# SW7201.net
KiCad netlist of a schematic drawn in Altium Designer
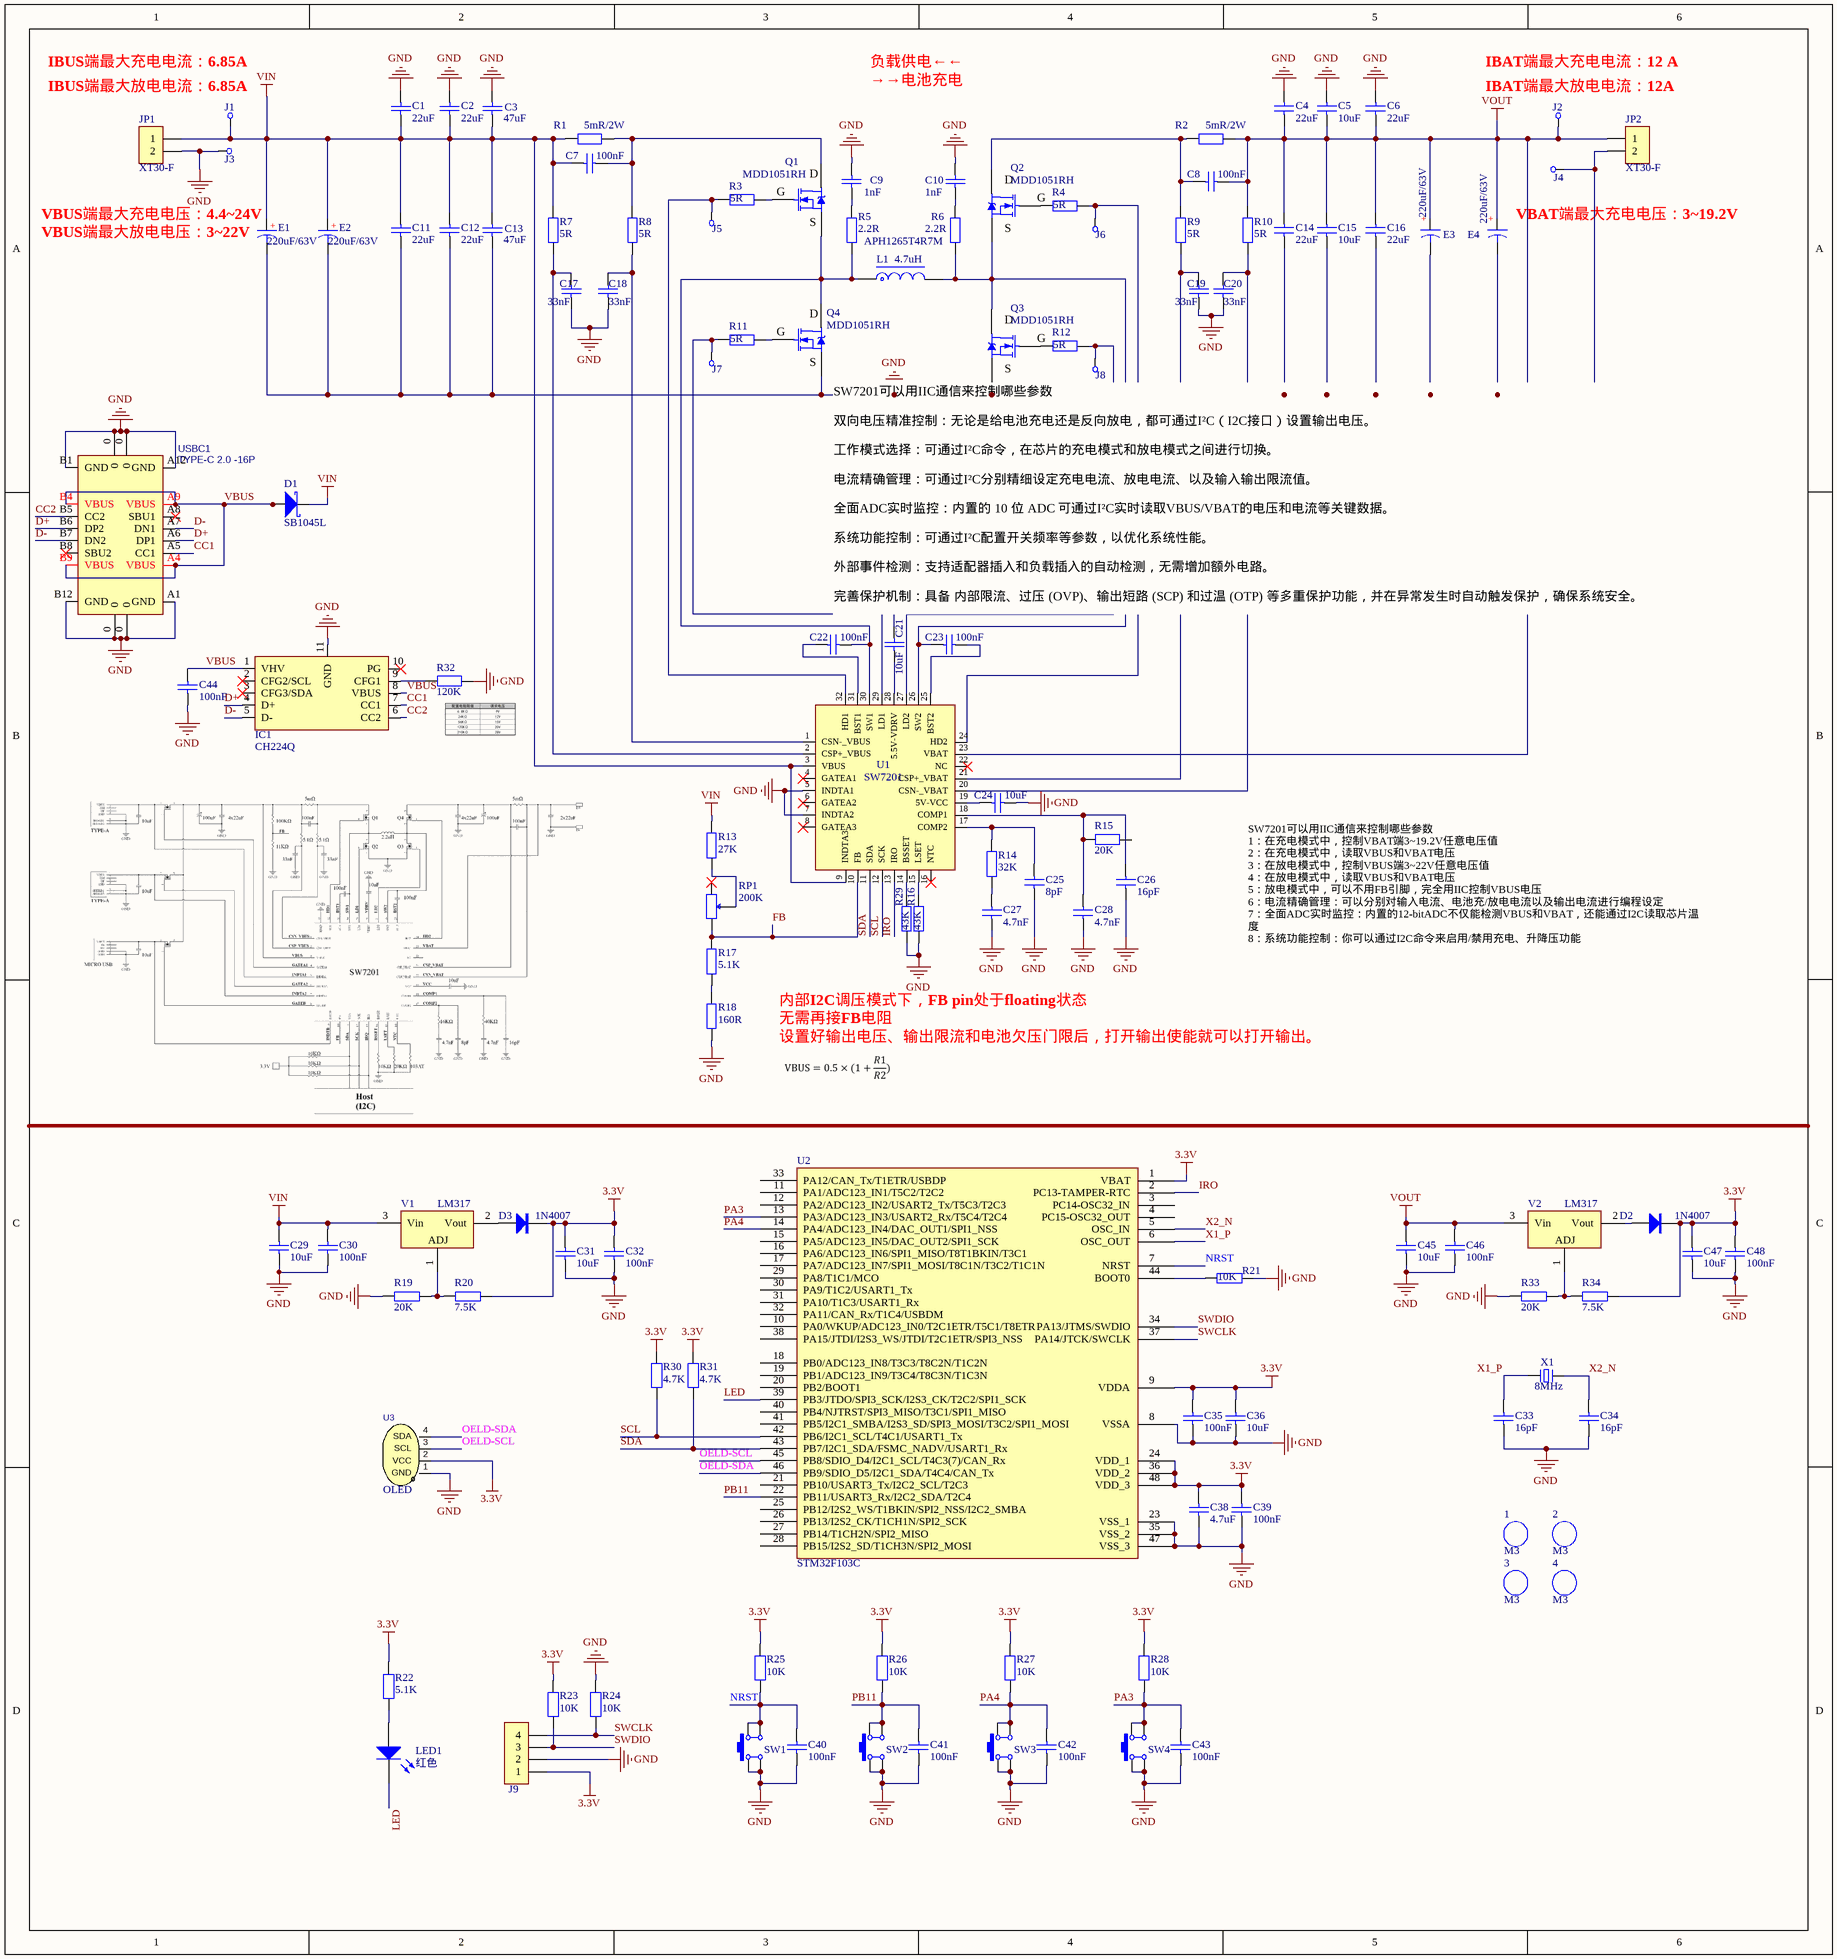
[diagram p0: SW7201.SchDoc]

(export (version "E")
  (design (tool "Eeschema 10.0.6"))
  (components
    (comp (ref "1")
      (value "M3")
      (footprint "M3 125X200")
      (description "铜柱孔")
      (libsource (lib "0.5 - 按键_开关_蜂鸣器_电池_测试点_Mark点_铜柱") (part "M3"))
    )
    (comp (ref "2")
      (value "M3")
      (footprint "M3 125X200")
      (description "铜柱孔")
      (libsource (lib "0.5 - 按键_开关_蜂鸣器_电池_测试点_Mark点_铜柱") (part "M3"))
    )
    (comp (ref "3")
      (value "M3")
      (footprint "M3 125X200")
      (description "铜柱孔")
      (libsource (lib "0.5 - 按键_开关_蜂鸣器_电池_测试点_Mark点_铜柱") (part "M3"))
    )
    (comp (ref "4")
      (value "M3")
      (footprint "M3 125X200")
      (description "铜柱孔")
      (libsource (lib "0.5 - 按键_开关_蜂鸣器_电池_测试点_Mark点_铜柱") (part "M3"))
    )
    (comp (ref "C1")
      (value "22uF")
      (footprint "C0805_L")
      (description "贴片电容/MLCC电容")
      (libsource (lib "0.1 - 电阻-电容-电感-保险丝-晶振-晶体-磁珠-电位器-法拉电容-馈通电容") (part "C"))
    )
    (comp (ref "C2")
      (value "22uF")
      (footprint "C0805_L")
      (description "贴片电容/MLCC电容")
      (libsource (lib "0.1 - 电阻-电容-电感-保险丝-晶振-晶体-磁珠-电位器-法拉电容-馈通电容") (part "C"))
    )
    (comp (ref "C3")
      (value "47uF")
      (footprint "C0805_L")
      (description "贴片电容/MLCC电容")
      (libsource (lib "0.1 - 电阻-电容-电感-保险丝-晶振-晶体-磁珠-电位器-法拉电容-馈通电容") (part "C"))
    )
    (comp (ref "C4")
      (value "22uF")
      (footprint "C0805_L")
      (description "贴片电容/MLCC电容")
      (libsource (lib "0.1 - 电阻-电容-电感-保险丝-晶振-晶体-磁珠-电位器-法拉电容-馈通电容") (part "C"))
    )
    (comp (ref "C5")
      (value "10uF")
      (footprint "C0805_L")
      (description "贴片电容/MLCC电容")
      (libsource (lib "0.1 - 电阻-电容-电感-保险丝-晶振-晶体-磁珠-电位器-法拉电容-馈通电容") (part "C"))
    )
    (comp (ref "C6")
      (value "22uF")
      (footprint "C0805_L")
      (description "贴片电容/MLCC电容")
      (libsource (lib "0.1 - 电阻-电容-电感-保险丝-晶振-晶体-磁珠-电位器-法拉电容-馈通电容") (part "C"))
    )
    (comp (ref "C7")
      (value "100nF")
      (footprint "C0805_L")
      (description "贴片电容/MLCC电容")
      (libsource (lib "0.1 - 电阻-电容-电感-保险丝-晶振-晶体-磁珠-电位器-法拉电容-馈通电容") (part "C"))
    )
    (comp (ref "C8")
      (value "100nF")
      (footprint "C0805_L")
      (description "贴片电容/MLCC电容")
      (libsource (lib "0.1 - 电阻-电容-电感-保险丝-晶振-晶体-磁珠-电位器-法拉电容-馈通电容") (part "C"))
    )
    (comp (ref "C9")
      (value "1nF")
      (footprint "C0805_L")
      (description "贴片电容/MLCC电容")
      (libsource (lib "0.1 - 电阻-电容-电感-保险丝-晶振-晶体-磁珠-电位器-法拉电容-馈通电容") (part "C"))
    )
    (comp (ref "C10")
      (value "1nF")
      (footprint "C0805_L")
      (description "贴片电容/MLCC电容")
      (libsource (lib "0.1 - 电阻-电容-电感-保险丝-晶振-晶体-磁珠-电位器-法拉电容-馈通电容") (part "C"))
    )
    (comp (ref "C11")
      (value "22uF")
      (footprint "C0805_L")
      (description "贴片电容/MLCC电容")
      (libsource (lib "0.1 - 电阻-电容-电感-保险丝-晶振-晶体-磁珠-电位器-法拉电容-馈通电容") (part "C"))
    )
    (comp (ref "C12")
      (value "22uF")
      (footprint "C0805_L")
      (description "贴片电容/MLCC电容")
      (libsource (lib "0.1 - 电阻-电容-电感-保险丝-晶振-晶体-磁珠-电位器-法拉电容-馈通电容") (part "C"))
    )
    (comp (ref "C13")
      (value "47uF")
      (footprint "C0805_L")
      (description "贴片电容/MLCC电容")
      (libsource (lib "0.1 - 电阻-电容-电感-保险丝-晶振-晶体-磁珠-电位器-法拉电容-馈通电容") (part "C"))
    )
    (comp (ref "C14")
      (value "22uF")
      (footprint "C0805_L")
      (description "贴片电容/MLCC电容")
      (libsource (lib "0.1 - 电阻-电容-电感-保险丝-晶振-晶体-磁珠-电位器-法拉电容-馈通电容") (part "C"))
    )
    (comp (ref "C15")
      (value "10uF")
      (footprint "C0805_L")
      (description "贴片电容/MLCC电容")
      (libsource (lib "0.1 - 电阻-电容-电感-保险丝-晶振-晶体-磁珠-电位器-法拉电容-馈通电容") (part "C"))
    )
    (comp (ref "C16")
      (value "22uF")
      (footprint "C0805_L")
      (description "贴片电容/MLCC电容")
      (libsource (lib "0.1 - 电阻-电容-电感-保险丝-晶振-晶体-磁珠-电位器-法拉电容-馈通电容") (part "C"))
    )
    (comp (ref "C17")
      (value "33nF")
      (footprint "C0805_L")
      (description "贴片电容/MLCC电容")
      (libsource (lib "0.1 - 电阻-电容-电感-保险丝-晶振-晶体-磁珠-电位器-法拉电容-馈通电容") (part "C"))
    )
    (comp (ref "C18")
      (value "33nF")
      (footprint "C0805_L")
      (description "贴片电容/MLCC电容")
      (libsource (lib "0.1 - 电阻-电容-电感-保险丝-晶振-晶体-磁珠-电位器-法拉电容-馈通电容") (part "C"))
    )
    (comp (ref "C19")
      (value "33nF")
      (footprint "C0805_L")
      (description "贴片电容/MLCC电容")
      (libsource (lib "0.1 - 电阻-电容-电感-保险丝-晶振-晶体-磁珠-电位器-法拉电容-馈通电容") (part "C"))
    )
    (comp (ref "C20")
      (value "33nF")
      (footprint "C0805_L")
      (description "贴片电容/MLCC电容")
      (libsource (lib "0.1 - 电阻-电容-电感-保险丝-晶振-晶体-磁珠-电位器-法拉电容-馈通电容") (part "C"))
    )
    (comp (ref "C21")
      (value "10uF")
      (footprint "C0805_L")
      (description "贴片电容/MLCC电容")
      (libsource (lib "0.1 - 电阻-电容-电感-保险丝-晶振-晶体-磁珠-电位器-法拉电容-馈通电容") (part "C"))
    )
    (comp (ref "C22")
      (value "100nF")
      (footprint "C0805_L")
      (description "贴片电容/MLCC电容")
      (libsource (lib "0.1 - 电阻-电容-电感-保险丝-晶振-晶体-磁珠-电位器-法拉电容-馈通电容") (part "C"))
    )
    (comp (ref "C23")
      (value "100nF")
      (footprint "C0805_L")
      (description "贴片电容/MLCC电容")
      (libsource (lib "0.1 - 电阻-电容-电感-保险丝-晶振-晶体-磁珠-电位器-法拉电容-馈通电容") (part "C"))
    )
    (comp (ref "C24")
      (value "10uF")
      (footprint "C0805_L")
      (description "贴片电容/MLCC电容")
      (libsource (lib "0.1 - 电阻-电容-电感-保险丝-晶振-晶体-磁珠-电位器-法拉电容-馈通电容") (part "C"))
    )
    (comp (ref "C25")
      (value "8pF")
      (footprint "C0805_L")
      (description "贴片电容/MLCC电容")
      (libsource (lib "0.1 - 电阻-电容-电感-保险丝-晶振-晶体-磁珠-电位器-法拉电容-馈通电容") (part "C"))
    )
    (comp (ref "C26")
      (value "16pF")
      (footprint "C0805_L")
      (description "贴片电容/MLCC电容")
      (libsource (lib "0.1 - 电阻-电容-电感-保险丝-晶振-晶体-磁珠-电位器-法拉电容-馈通电容") (part "C"))
    )
    (comp (ref "C27")
      (value "4.7nF")
      (footprint "C0805_L")
      (description "贴片电容/MLCC电容")
      (libsource (lib "0.1 - 电阻-电容-电感-保险丝-晶振-晶体-磁珠-电位器-法拉电容-馈通电容") (part "C"))
    )
    (comp (ref "C28")
      (value "4.7nF")
      (footprint "C0805_L")
      (description "贴片电容/MLCC电容")
      (libsource (lib "0.1 - 电阻-电容-电感-保险丝-晶振-晶体-磁珠-电位器-法拉电容-馈通电容") (part "C"))
    )
    (comp (ref "C29")
      (value "10uF")
      (footprint "C0805_L")
      (description "贴片电容/MLCC电容")
      (libsource (lib "0.1 - 电阻-电容-电感-保险丝-晶振-晶体-磁珠-电位器-法拉电容-馈通电容") (part "C"))
    )
    (comp (ref "C30")
      (value "100nF")
      (footprint "C0805_L")
      (description "贴片电容/MLCC电容")
      (libsource (lib "0.1 - 电阻-电容-电感-保险丝-晶振-晶体-磁珠-电位器-法拉电容-馈通电容") (part "C"))
    )
    (comp (ref "C31")
      (value "10uF")
      (footprint "C0805_L")
      (description "贴片电容/MLCC电容")
      (libsource (lib "0.1 - 电阻-电容-电感-保险丝-晶振-晶体-磁珠-电位器-法拉电容-馈通电容") (part "C"))
    )
    (comp (ref "C32")
      (value "100nF")
      (footprint "C0805_L")
      (description "贴片电容/MLCC电容")
      (libsource (lib "0.1 - 电阻-电容-电感-保险丝-晶振-晶体-磁珠-电位器-法拉电容-馈通电容") (part "C"))
    )
    (comp (ref "C33")
      (value "16pF")
      (footprint "C0805_L")
      (description "贴片电容/MLCC电容")
      (libsource (lib "0.1 - 电阻-电容-电感-保险丝-晶振-晶体-磁珠-电位器-法拉电容-馈通电容") (part "C"))
    )
    (comp (ref "C34")
      (value "16pF")
      (footprint "C0805_L")
      (description "贴片电容/MLCC电容")
      (libsource (lib "0.1 - 电阻-电容-电感-保险丝-晶振-晶体-磁珠-电位器-法拉电容-馈通电容") (part "C"))
    )
    (comp (ref "C35")
      (value "100nF")
      (footprint "C0805_L")
      (description "贴片电容/MLCC电容")
      (libsource (lib "0.1 - 电阻-电容-电感-保险丝-晶振-晶体-磁珠-电位器-法拉电容-馈通电容") (part "C"))
    )
    (comp (ref "C36")
      (value "10uF")
      (footprint "C0805_L")
      (description "贴片电容/MLCC电容")
      (libsource (lib "0.1 - 电阻-电容-电感-保险丝-晶振-晶体-磁珠-电位器-法拉电容-馈通电容") (part "C"))
    )
    (comp (ref "C38")
      (value "4.7uF")
      (footprint "C0805_L")
      (description "贴片电容/MLCC电容")
      (libsource (lib "0.1 - 电阻-电容-电感-保险丝-晶振-晶体-磁珠-电位器-法拉电容-馈通电容") (part "C"))
    )
    (comp (ref "C39")
      (value "100nF")
      (footprint "C0805_L")
      (description "贴片电容/MLCC电容")
      (libsource (lib "0.1 - 电阻-电容-电感-保险丝-晶振-晶体-磁珠-电位器-法拉电容-馈通电容") (part "C"))
    )
    (comp (ref "C40")
      (value "100nF")
      (footprint "C0805_L")
      (description "贴片电容/MLCC电容")
      (libsource (lib "0.1 - 电阻-电容-电感-保险丝-晶振-晶体-磁珠-电位器-法拉电容-馈通电容") (part "C"))
    )
    (comp (ref "C41")
      (value "100nF")
      (footprint "C0805_L")
      (description "贴片电容/MLCC电容")
      (libsource (lib "0.1 - 电阻-电容-电感-保险丝-晶振-晶体-磁珠-电位器-法拉电容-馈通电容") (part "C"))
    )
    (comp (ref "C42")
      (value "100nF")
      (footprint "C0805_L")
      (description "贴片电容/MLCC电容")
      (libsource (lib "0.1 - 电阻-电容-电感-保险丝-晶振-晶体-磁珠-电位器-法拉电容-馈通电容") (part "C"))
    )
    (comp (ref "C43")
      (value "100nF")
      (footprint "C0805_L")
      (description "贴片电容/MLCC电容")
      (libsource (lib "0.1 - 电阻-电容-电感-保险丝-晶振-晶体-磁珠-电位器-法拉电容-馈通电容") (part "C"))
    )
    (comp (ref "C44")
      (value "100nF")
      (footprint "C0805_L")
      (description "贴片电容/MLCC电容")
      (libsource (lib "0.1 - 电阻-电容-电感-保险丝-晶振-晶体-磁珠-电位器-法拉电容-馈通电容") (part "C"))
    )
    (comp (ref "C45")
      (value "10uF")
      (footprint "C0805_L")
      (description "贴片电容/MLCC电容")
      (libsource (lib "0.1 - 电阻-电容-电感-保险丝-晶振-晶体-磁珠-电位器-法拉电容-馈通电容") (part "C"))
    )
    (comp (ref "C46")
      (value "100nF")
      (footprint "C0805_L")
      (description "贴片电容/MLCC电容")
      (libsource (lib "0.1 - 电阻-电容-电感-保险丝-晶振-晶体-磁珠-电位器-法拉电容-馈通电容") (part "C"))
    )
    (comp (ref "C47")
      (value "10uF")
      (footprint "C0805_L")
      (description "贴片电容/MLCC电容")
      (libsource (lib "0.1 - 电阻-电容-电感-保险丝-晶振-晶体-磁珠-电位器-法拉电容-馈通电容") (part "C"))
    )
    (comp (ref "C48")
      (value "100nF")
      (footprint "C0805_L")
      (description "贴片电容/MLCC电容")
      (libsource (lib "0.1 - 电阻-电容-电感-保险丝-晶振-晶体-磁珠-电位器-法拉电容-馈通电容") (part "C"))
    )
    (comp (ref "D1")
      (value "SB1045L")
      (footprint "TO-277_3P-L5.4-W4.0")
      (libsource (lib "0.2 - 二极管-TVS-ESD-整流桥-放电管") (part "SB1045L"))
    )
    (comp (ref "D2")
      (value "1N4007")
      (footprint "SOD-123")
      (description "整流二极管")
      (libsource (lib "0.2 - 二极管-TVS-ESD-整流桥-放电管") (part "1N4007"))
    )
    (comp (ref "D3")
      (value "1N4007")
      (footprint "SOD-123")
      (description "整流二极管")
      (libsource (lib "0.2 - 二极管-TVS-ESD-整流桥-放电管") (part "1N4007"))
    )
    (comp (ref "E1")
      (value "220uF/63V")
      (footprint "CT 5.0*10*13 - R")
      (description "直插固态电容")
      (libsource (lib "") (part "CS_1"))
    )
    (comp (ref "E2")
      (value "220uF/63V")
      (footprint "CT 5.0*10*13 - R")
      (description "直插固态电容")
      (libsource (lib "") (part "CS_1"))
    )
    (comp (ref "E3")
      (value "220uF/63V")
      (footprint "CT 5.0*10*13 - R")
      (description "直插固态电容")
      (libsource (lib "0.1 - 电阻-电容-电感-保险丝-晶振-晶体-磁珠-电位器-法拉电容-馈通电容") (part "CS"))
    )
    (comp (ref "E4")
      (value "220uF/63V")
      (footprint "CT 5.0*10*13 - R")
      (description "直插固态电容")
      (libsource (lib "0.1 - 电阻-电容-电感-保险丝-晶振-晶体-磁珠-电位器-法拉电容-馈通电容") (part "CS"))
    )
    (comp (ref "IC1")
      (value "CH224Q")
      (footprint "DFN-10_L2.0-W2")
      (libsource (lib "1.8 - CH340系列编程器芯片") (part "CH224Q"))
    )
    (comp (ref "J1")
      (value "CHECK")
      (footprint "CHECK-A")
      (description "测试点")
      (libsource (lib "课程库") (part "CHECK"))
    )
    (comp (ref "J2")
      (value "CHECK")
      (footprint "CHECK-A")
      (description "测试点")
      (libsource (lib "课程库") (part "CHECK"))
    )
    (comp (ref "J3")
      (value "CHECK")
      (footprint "CHECK-A")
      (description "测试点")
      (libsource (lib "课程库") (part "CHECK"))
    )
    (comp (ref "J4")
      (value "CHECK")
      (footprint "CHECK-A")
      (description "测试点")
      (libsource (lib "课程库") (part "CHECK"))
    )
    (comp (ref "J5")
      (value "CHECK")
      (footprint "CHECK-A")
      (description "测试点")
      (libsource (lib "课程库") (part "CHECK"))
    )
    (comp (ref "J6")
      (value "CHECK")
      (footprint "CHECK-A")
      (description "测试点")
      (libsource (lib "课程库") (part "CHECK"))
    )
    (comp (ref "J7")
      (value "CHECK")
      (footprint "CHECK-A")
      (description "测试点")
      (libsource (lib "课程库") (part "CHECK"))
    )
    (comp (ref "J8")
      (value "CHECK")
      (footprint "CHECK-A")
      (description "测试点")
      (libsource (lib "课程库") (part "CHECK"))
    )
    (comp (ref "J9")
      (value "HDR-1X4")
      (footprint "HDR2.54-LI-4P")
      (description "4P接插件")
      (libsource (lib "5.5 - 2.54mm连接器(KF2EDGK_XH2.54_2.54排针排母)") (part "Header 4"))
    )
    (comp (ref "JP1")
      (value "XT30-F")
      (footprint "XT30PW-F")
      (description "XT30母座")
      (libsource (lib "") (part "XT30-F_1"))
    )
    (comp (ref "JP2")
      (value "XT30-F")
      (footprint "XT30PW-F")
      (description "XT30母座")
      (libsource (lib "0.6 - 电源_音频_USB Type-C_HDMI_XT60_5557_D-SUB_RJ45_SD-TF_SIM插座") (part "XT30-F"))
    )
    (comp (ref "L1")
      (value "4.7uH")
      (footprint "SMD,13.5x12.6mm")
      (description "一体成型电感")
      (libsource (lib "0.1 - 电阻-电容-电感-保险丝-晶振-晶体-磁珠-电位器-法拉电容-馈通电容") (part "L-Molding Choke"))
    )
    (comp (ref "LED1")
      (value "红色")
      (footprint "LED0805_G")
      (description "贴片LED")
      (libsource (lib "0.3 - LED发光二极管-IR二极管_接收管-光耦") (part "LED"))
    )
    (comp (ref "Q1")
      (value "MDD1051RH")
      (footprint "TO252")
      (description "N沟道 30V/80A")
      (libsource (lib "0.4 - 三极管-场效应管-可控硅") (part "NCE3080"))
    )
    (comp (ref "Q2")
      (value "MDD1051RH")
      (footprint "TO252")
      (description "N沟道 30V/80A")
      (libsource (lib "0.4 - 三极管-场效应管-可控硅") (part "NCE3080"))
    )
    (comp (ref "Q3")
      (value "MDD1051RH")
      (footprint "TO252")
      (description "N沟道 30V/80A")
      (libsource (lib "0.4 - 三极管-场效应管-可控硅") (part "NCE3080"))
    )
    (comp (ref "Q4")
      (value "MDD1051RH")
      (footprint "TO252")
      (description "N沟道 30V/80A")
      (libsource (lib "0.4 - 三极管-场效应管-可控硅") (part "NCE3080"))
    )
    (comp (ref "R1")
      (value "5mR/2W")
      (footprint "R2512_M")
      (description "贴片电阻")
      (libsource (lib "0.1 - 电阻-电容-电感-保险丝-晶振-晶体-磁珠-电位器-法拉电容-馈通电容") (part "R"))
    )
    (comp (ref "R2")
      (value "5mR/2W")
      (footprint "R2512_M")
      (description "贴片电阻")
      (libsource (lib "0.1 - 电阻-电容-电感-保险丝-晶振-晶体-磁珠-电位器-法拉电容-馈通电容") (part "R"))
    )
    (comp (ref "R3")
      (value "5R")
      (footprint "R0805_L")
      (description "贴片电阻")
      (libsource (lib "0.1 - 电阻-电容-电感-保险丝-晶振-晶体-磁珠-电位器-法拉电容-馈通电容") (part "R"))
    )
    (comp (ref "R4")
      (value "5R")
      (footprint "R0805_L")
      (description "贴片电阻")
      (libsource (lib "0.1 - 电阻-电容-电感-保险丝-晶振-晶体-磁珠-电位器-法拉电容-馈通电容") (part "R"))
    )
    (comp (ref "R5")
      (value "2.2R")
      (footprint "R0805_L")
      (description "贴片电阻")
      (libsource (lib "0.1 - 电阻-电容-电感-保险丝-晶振-晶体-磁珠-电位器-法拉电容-馈通电容") (part "R"))
    )
    (comp (ref "R6")
      (value "2.2R")
      (footprint "R0805_L")
      (description "贴片电阻")
      (libsource (lib "0.1 - 电阻-电容-电感-保险丝-晶振-晶体-磁珠-电位器-法拉电容-馈通电容") (part "R"))
    )
    (comp (ref "R7")
      (value "5R")
      (footprint "R0805_L")
      (description "贴片电阻")
      (libsource (lib "0.1 - 电阻-电容-电感-保险丝-晶振-晶体-磁珠-电位器-法拉电容-馈通电容") (part "R"))
    )
    (comp (ref "R8")
      (value "5R")
      (footprint "R0805_L")
      (description "贴片电阻")
      (libsource (lib "0.1 - 电阻-电容-电感-保险丝-晶振-晶体-磁珠-电位器-法拉电容-馈通电容") (part "R"))
    )
    (comp (ref "R9")
      (value "5R")
      (footprint "R0805_L")
      (description "贴片电阻")
      (libsource (lib "0.1 - 电阻-电容-电感-保险丝-晶振-晶体-磁珠-电位器-法拉电容-馈通电容") (part "R"))
    )
    (comp (ref "R10")
      (value "5R")
      (footprint "R0805_L")
      (description "贴片电阻")
      (libsource (lib "0.1 - 电阻-电容-电感-保险丝-晶振-晶体-磁珠-电位器-法拉电容-馈通电容") (part "R"))
    )
    (comp (ref "R11")
      (value "5R")
      (footprint "R0805_L")
      (description "贴片电阻")
      (libsource (lib "0.1 - 电阻-电容-电感-保险丝-晶振-晶体-磁珠-电位器-法拉电容-馈通电容") (part "R"))
    )
    (comp (ref "R12")
      (value "5R")
      (footprint "R0805_L")
      (description "贴片电阻")
      (libsource (lib "0.1 - 电阻-电容-电感-保险丝-晶振-晶体-磁珠-电位器-法拉电容-馈通电容") (part "R"))
    )
    (comp (ref "R13")
      (value "27K")
      (footprint "R0805_L")
      (description "贴片电阻")
      (libsource (lib "0.1 - 电阻-电容-电感-保险丝-晶振-晶体-磁珠-电位器-法拉电容-馈通电容") (part "R"))
    )
    (comp (ref "R14")
      (value "32K")
      (footprint "R0805_L")
      (description "贴片电阻")
      (libsource (lib "0.1 - 电阻-电容-电感-保险丝-晶振-晶体-磁珠-电位器-法拉电容-馈通电容") (part "R"))
    )
    (comp (ref "R15")
      (value "20K")
      (footprint "R0805_L")
      (description "贴片电阻")
      (libsource (lib "0.1 - 电阻-电容-电感-保险丝-晶振-晶体-磁珠-电位器-法拉电容-馈通电容") (part "R"))
    )
    (comp (ref "R16")
      (value "43K")
      (footprint "R0805_L")
      (description "贴片电阻")
      (libsource (lib "0.1 - 电阻-电容-电感-保险丝-晶振-晶体-磁珠-电位器-法拉电容-馈通电容") (part "R"))
    )
    (comp (ref "R17")
      (value "5.1K")
      (footprint "R0805_L")
      (description "贴片电阻")
      (libsource (lib "0.1 - 电阻-电容-电感-保险丝-晶振-晶体-磁珠-电位器-法拉电容-馈通电容") (part "R"))
    )
    (comp (ref "R18")
      (value "160R")
      (footprint "R0805_L")
      (description "贴片电阻")
      (libsource (lib "0.1 - 电阻-电容-电感-保险丝-晶振-晶体-磁珠-电位器-法拉电容-馈通电容") (part "R"))
    )
    (comp (ref "R19")
      (value "20K")
      (footprint "R0805_L")
      (description "贴片电阻")
      (libsource (lib "0.1 - 电阻-电容-电感-保险丝-晶振-晶体-磁珠-电位器-法拉电容-馈通电容") (part "R"))
    )
    (comp (ref "R20")
      (value "7.5K")
      (footprint "R0805_L")
      (description "贴片电阻")
      (libsource (lib "0.1 - 电阻-电容-电感-保险丝-晶振-晶体-磁珠-电位器-法拉电容-馈通电容") (part "R"))
    )
    (comp (ref "R21")
      (value "10K")
      (footprint "R0805_L")
      (description "贴片电阻")
      (libsource (lib "0.1 - 电阻-电容-电感-保险丝-晶振-晶体-磁珠-电位器-法拉电容-馈通电容") (part "R"))
    )
    (comp (ref "R22")
      (value "5.1K")
      (footprint "R0805_L")
      (description "贴片电阻")
      (libsource (lib "0.1 - 电阻-电容-电感-保险丝-晶振-晶体-磁珠-电位器-法拉电容-馈通电容") (part "R"))
    )
    (comp (ref "R23")
      (value "10K")
      (footprint "R0805_L")
      (description "贴片电阻")
      (libsource (lib "0.1 - 电阻-电容-电感-保险丝-晶振-晶体-磁珠-电位器-法拉电容-馈通电容") (part "R"))
    )
    (comp (ref "R24")
      (value "10K")
      (footprint "R0805_L")
      (description "贴片电阻")
      (libsource (lib "0.1 - 电阻-电容-电感-保险丝-晶振-晶体-磁珠-电位器-法拉电容-馈通电容") (part "R"))
    )
    (comp (ref "R25")
      (value "10K")
      (footprint "R0805_L")
      (description "贴片电阻")
      (libsource (lib "0.1 - 电阻-电容-电感-保险丝-晶振-晶体-磁珠-电位器-法拉电容-馈通电容") (part "R"))
    )
    (comp (ref "R26")
      (value "10K")
      (footprint "R0805_L")
      (description "贴片电阻")
      (libsource (lib "0.1 - 电阻-电容-电感-保险丝-晶振-晶体-磁珠-电位器-法拉电容-馈通电容") (part "R"))
    )
    (comp (ref "R27")
      (value "10K")
      (footprint "R0805_L")
      (description "贴片电阻")
      (libsource (lib "0.1 - 电阻-电容-电感-保险丝-晶振-晶体-磁珠-电位器-法拉电容-馈通电容") (part "R"))
    )
    (comp (ref "R28")
      (value "10K")
      (footprint "R0805_L")
      (description "贴片电阻")
      (libsource (lib "0.1 - 电阻-电容-电感-保险丝-晶振-晶体-磁珠-电位器-法拉电容-馈通电容") (part "R"))
    )
    (comp (ref "R29")
      (value "43K")
      (footprint "R0805_L")
      (description "贴片电阻")
      (libsource (lib "0.1 - 电阻-电容-电感-保险丝-晶振-晶体-磁珠-电位器-法拉电容-馈通电容") (part "R"))
    )
    (comp (ref "R30")
      (value "4.7K")
      (footprint "R0805_L")
      (description "贴片电阻")
      (libsource (lib "0.1 - 电阻-电容-电感-保险丝-晶振-晶体-磁珠-电位器-法拉电容-馈通电容") (part "R"))
    )
    (comp (ref "R31")
      (value "4.7K")
      (footprint "R0805_L")
      (description "贴片电阻")
      (libsource (lib "0.1 - 电阻-电容-电感-保险丝-晶振-晶体-磁珠-电位器-法拉电容-馈通电容") (part "R"))
    )
    (comp (ref "R32")
      (value "120K")
      (footprint "R0805_L")
      (description "贴片电阻")
      (libsource (lib "0.1 - 电阻-电容-电感-保险丝-晶振-晶体-磁珠-电位器-法拉电容-馈通电容") (part "R"))
    )
    (comp (ref "R33")
      (value "20K")
      (footprint "R0805_L")
      (description "贴片电阻")
      (libsource (lib "0.1 - 电阻-电容-电感-保险丝-晶振-晶体-磁珠-电位器-法拉电容-馈通电容") (part "R"))
    )
    (comp (ref "R34")
      (value "7.5K")
      (footprint "R0805_L")
      (description "贴片电阻")
      (libsource (lib "0.1 - 电阻-电容-电感-保险丝-晶振-晶体-磁珠-电位器-法拉电容-馈通电容") (part "R"))
    )
    (comp (ref "RP1")
      (value "200K")
      (footprint "3296W")
      (description "单联电位器")
      (libsource (lib "0.1 - 电阻-电容-电感-保险丝-晶振-晶体-磁珠-电位器-法拉电容-馈通电容") (part "RP"))
    )
    (comp (ref "SW1")
      (value "4.5x4.5x3.8")
      (footprint "SW SMD-4.5*4.5*3.8")
      (description "贴片4.5x4.5轻触开关")
      (libsource (lib "0.5 - 按键_开关_蜂鸣器_电池_测试点_Mark点_铜柱") (part "SW SMD-4.5x4.5"))
    )
    (comp (ref "SW2")
      (value "4.5x4.5x3.8")
      (footprint "SW SMD-4.5*4.5*3.8")
      (description "贴片4.5x4.5轻触开关")
      (libsource (lib "0.5 - 按键_开关_蜂鸣器_电池_测试点_Mark点_铜柱") (part "SW SMD-4.5x4.5"))
    )
    (comp (ref "SW3")
      (value "4.5x4.5x3.8")
      (footprint "SW SMD-4.5*4.5*3.8")
      (description "贴片4.5x4.5轻触开关")
      (libsource (lib "0.5 - 按键_开关_蜂鸣器_电池_测试点_Mark点_铜柱") (part "SW SMD-4.5x4.5"))
    )
    (comp (ref "SW4")
      (value "4.5x4.5x3.8")
      (footprint "SW SMD-4.5*4.5*3.8")
      (description "贴片4.5x4.5轻触开关")
      (libsource (lib "0.5 - 按键_开关_蜂鸣器_电池_测试点_Mark点_铜柱") (part "SW SMD-4.5x4.5"))
    )
    (comp (ref "U1")
      (value "SW7201")
      (footprint "QFN32_L4.0-W4.0-P0.4")
      (description "3~35V支持I2C控制的高效率双向升降压充放电控制器")
      (libsource (lib "0.7 - 电源类芯片") (part "SW7201"))
    )
    (comp (ref "U2")
      (value "STM32F103C")
      (footprint "LQFP-48_M")
      (description "STM32单片机48引脚")
      (libsource (lib "课程库") (part "STM32F103C"))
    )
    (comp (ref "U3")
      (value "OLED")
      (footprint "OLED")
      (description "0.96OLED")
      (libsource (lib "课程库") (part "OLED"))
    )
    (comp (ref "USBC1")
      (value "TYPE-C 2.0 -16P")
      (footprint "USB-C-SMD_16P")
      (description "USB2.0_Type-C_16Pin母座")
      (libsource (lib "0.6 - 电源_音频_USB Type-C_HDMI_XT60_5557_D-SUB_RJ45_SD-TF_SIM插座") (part "USB2.0_Type-C_16Pin"))
    )
    (comp (ref "V1")
      (value "LM317")
      (footprint "SOT223_M")
      (description "可调线性稳压芯片")
      (libsource (lib "0.7 - 电源类芯片") (part "LM317"))
    )
    (comp (ref "V2")
      (value "LM317")
      (footprint "SOT223_M")
      (description "可调线性稳压芯片")
      (libsource (lib "0.7 - 电源类芯片") (part "LM317"))
    )
    (comp (ref "X1")
      (value "8MHz")
      (footprint "XTAL-5032-2P")
      (description "2脚无源晶振(谐振器）")
      (libsource (lib "0.1 - 电阻-电容-电感-保险丝-晶振-晶体-磁珠-电位器-法拉电容-馈通电容") (part "XTAL-2P"))
    )
  )
  (nets
    (net (code "1") (name "/CC1") (class "Default")
      (node (ref "IC1") (pin "7") (pinfunction "CC1_7") (pintype "passive"))
      (node (ref "USBC1") (pin "A5") (pinfunction "CC1_A5") (pintype "passive"))
    )
    (net (code "2") (name "/CC2") (class "Default")
      (node (ref "IC1") (pin "6") (pinfunction "CC2_6") (pintype "passive"))
      (node (ref "USBC1") (pin "B5") (pinfunction "CC2_B5") (pintype "passive"))
    )
    (net (code "3") (name "/D+") (class "Default")
      (node (ref "IC1") (pin "4") (pinfunction "D+_4") (pintype "passive"))
      (node (ref "USBC1") (pin "A6") (pinfunction "DP1_A6") (pintype "passive"))
      (node (ref "USBC1") (pin "B6") (pinfunction "DP2_B6") (pintype "passive"))
    )
    (net (code "4") (name "/D-") (class "Default")
      (node (ref "IC1") (pin "5") (pinfunction "D-_5") (pintype "passive"))
      (node (ref "USBC1") (pin "A7") (pinfunction "DN1_A7") (pintype "passive"))
      (node (ref "USBC1") (pin "B7") (pinfunction "DN2_B7") (pintype "passive"))
    )
    (net (code "5") (name "/FB") (class "Default")
      (node (ref "R17") (pin "1") (pinfunction "1_1") (pintype "passive"))
      (node (ref "RP1") (pin "1") (pinfunction "1_1") (pintype "passive"))
      (node (ref "U1") (pin "10") (pinfunction "FB_10") (pintype "passive"))
    )
    (net (code "6") (name "/IRO") (class "Default")
      (node (ref "U1") (pin "13") (pinfunction "IRO_13") (pintype "passive"))
      (node (ref "U2") (pin "2") (pinfunction "PC13-TAMPER-RTC_2") (pintype "passive"))
    )
    (net (code "7") (name "/LED") (class "Default")
      (node (ref "LED1") (pin "2") (pinfunction "K_2") (pintype "passive"))
      (node (ref "U2") (pin "39") (pinfunction "PB3/JTDO/SPI3_SCK/I2S3_CK/T2C2/SPI1_SCK_39") (pintype "passive"))
    )
    (net (code "8") (name "/NRST") (class "Default")
      (node (ref "C40") (pin "2") (pinfunction "2_2") (pintype "passive"))
      (node (ref "R25") (pin "2") (pinfunction "2_2") (pintype "passive"))
      (node (ref "SW1") (pin "2") (pinfunction "2_2") (pintype "passive"))
      (node (ref "SW1") (pin "3") (pinfunction "3_3") (pintype "passive"))
      (node (ref "U2") (pin "7") (pinfunction "NRST_7") (pintype "passive"))
    )
    (net (code "9") (name "/OELD-SCL") (class "Default")
      (node (ref "U2") (pin "45") (pinfunction "PB8/SDIO_D4/I2C1_SCL/T4C3(7)/CAN_Rx_45") (pintype "passive"))
      (node (ref "U3") (pin "3") (pinfunction "SCL_3") (pintype "passive"))
    )
    (net (code "10") (name "/OELD-SDA") (class "Default")
      (node (ref "U2") (pin "46") (pinfunction "PB9/SDIO_D5/I2C1_SDA/T4C4/CAN_Tx_46") (pintype "passive"))
      (node (ref "U3") (pin "4") (pinfunction "SDA_4") (pintype "passive"))
    )
    (net (code "11") (name "/PA3") (class "Default")
      (node (ref "C43") (pin "2") (pinfunction "2_2") (pintype "passive"))
      (node (ref "R28") (pin "2") (pinfunction "2_2") (pintype "passive"))
      (node (ref "SW4") (pin "2") (pinfunction "2_2") (pintype "passive"))
      (node (ref "SW4") (pin "3") (pinfunction "3_3") (pintype "passive"))
      (node (ref "U2") (pin "13") (pinfunction "PA3/ADC123_IN3/USART2_Rx/T5C4/T2C4_13") (pintype "passive"))
    )
    (net (code "12") (name "/PA4") (class "Default")
      (node (ref "C42") (pin "2") (pinfunction "2_2") (pintype "passive"))
      (node (ref "R27") (pin "2") (pinfunction "2_2") (pintype "passive"))
      (node (ref "SW3") (pin "2") (pinfunction "2_2") (pintype "passive"))
      (node (ref "SW3") (pin "3") (pinfunction "3_3") (pintype "passive"))
      (node (ref "U2") (pin "14") (pinfunction "PA4/ADC123_IN4/DAC_OUT1/SPI1_NSS_14") (pintype "passive"))
    )
    (net (code "13") (name "/PB11") (class "Default")
      (node (ref "C41") (pin "2") (pinfunction "2_2") (pintype "passive"))
      (node (ref "R26") (pin "2") (pinfunction "2_2") (pintype "passive"))
      (node (ref "SW2") (pin "2") (pinfunction "2_2") (pintype "passive"))
      (node (ref "SW2") (pin "3") (pinfunction "3_3") (pintype "passive"))
      (node (ref "U2") (pin "22") (pinfunction "PB11/USART3_Rx/I2C2_SDA/T2C4_22") (pintype "passive"))
    )
    (net (code "14") (name "/SCL") (class "Default")
      (node (ref "R30") (pin "2") (pinfunction "2_2") (pintype "passive"))
      (node (ref "U1") (pin "12") (pinfunction "SCK_12") (pintype "passive"))
      (node (ref "U2") (pin "42") (pinfunction "PB6/I2C1_SCL/T4C1/USART1_Tx_42") (pintype "passive"))
    )
    (net (code "15") (name "/SDA") (class "Default")
      (node (ref "R31") (pin "2") (pinfunction "2_2") (pintype "passive"))
      (node (ref "U1") (pin "11") (pinfunction "SDA_11") (pintype "passive"))
      (node (ref "U2") (pin "43") (pinfunction "PB7/I2C1_SDA/FSMC_NADV/USART1_Rx_43") (pintype "passive"))
    )
    (net (code "16") (name "/SWCLK") (class "Default")
      (node (ref "J9") (pin "4") (pinfunction "4_4") (pintype "passive"))
      (node (ref "R24") (pin "2") (pinfunction "2_2") (pintype "passive"))
      (node (ref "U2") (pin "37") (pinfunction "PA14/JTCK/SWCLK_37") (pintype "passive"))
    )
    (net (code "17") (name "/SWDIO") (class "Default")
      (node (ref "J9") (pin "3") (pinfunction "3_3") (pintype "passive"))
      (node (ref "R23") (pin "2") (pinfunction "2_2") (pintype "passive"))
      (node (ref "U2") (pin "34") (pinfunction "PA13/JTMS/SWDIO_34") (pintype "passive"))
    )
    (net (code "18") (name "/VBUS") (class "Default")
      (node (ref "C44") (pin "2") (pinfunction "2_2") (pintype "passive"))
      (node (ref "D1") (pin "1") (pinfunction "A_1") (pintype "passive"))
      (node (ref "D1") (pin "3") (pinfunction "A_3") (pintype "passive"))
      (node (ref "IC1") (pin "1") (pinfunction "VHV_1") (pintype "passive"))
      (node (ref "IC1") (pin "8") (pinfunction "VBUS_8") (pintype "passive"))
      (node (ref "USBC1") (pin "A4") (pinfunction "VBUS_A4") (pintype "passive"))
      (node (ref "USBC1") (pin "A9") (pinfunction "VBUS_A9") (pintype "passive"))
      (node (ref "USBC1") (pin "B4") (pinfunction "VBUS_B4") (pintype "passive"))
      (node (ref "USBC1") (pin "B9") (pinfunction "VBUS_B9") (pintype "passive"))
    )
    (net (code "19") (name "/X1_P") (class "Default")
      (node (ref "C33") (pin "2") (pinfunction "2_2") (pintype "passive"))
      (node (ref "U2") (pin "6") (pinfunction "OSC_OUT_6") (pintype "passive"))
      (node (ref "X1") (pin "1") (pinfunction "1_1") (pintype "passive"))
    )
    (net (code "20") (name "/X2_N") (class "Default")
      (node (ref "C34") (pin "2") (pinfunction "2_2") (pintype "passive"))
      (node (ref "U2") (pin "5") (pinfunction "OSC_IN_5") (pintype "passive"))
      (node (ref "X1") (pin "2") (pinfunction "2_2") (pintype "passive"))
    )
    (net (code "21") (name "3.3V") (class "Default")
      (node (ref "C31") (pin "2") (pinfunction "2_2") (pintype "passive"))
      (node (ref "C32") (pin "2") (pinfunction "2_2") (pintype "passive"))
      (node (ref "C35") (pin "2") (pinfunction "2_2") (pintype "passive"))
      (node (ref "C36") (pin "2") (pinfunction "2_2") (pintype "passive"))
      (node (ref "C38") (pin "2") (pinfunction "2_2") (pintype "passive"))
      (node (ref "C39") (pin "2") (pinfunction "2_2") (pintype "passive"))
      (node (ref "C47") (pin "2") (pinfunction "2_2") (pintype "passive"))
      (node (ref "C48") (pin "2") (pinfunction "2_2") (pintype "passive"))
      (node (ref "D2") (pin "2") (pinfunction "K_2") (pintype "passive"))
      (node (ref "D3") (pin "2") (pinfunction "K_2") (pintype "passive"))
      (node (ref "J9") (pin "1") (pinfunction "1_1") (pintype "passive"))
      (node (ref "R20") (pin "2") (pinfunction "2_2") (pintype "passive"))
      (node (ref "R22") (pin "1") (pinfunction "1_1") (pintype "passive"))
      (node (ref "R23") (pin "1") (pinfunction "1_1") (pintype "passive"))
      (node (ref "R25") (pin "1") (pinfunction "1_1") (pintype "passive"))
      (node (ref "R26") (pin "1") (pinfunction "1_1") (pintype "passive"))
      (node (ref "R27") (pin "1") (pinfunction "1_1") (pintype "passive"))
      (node (ref "R28") (pin "1") (pinfunction "1_1") (pintype "passive"))
      (node (ref "R30") (pin "1") (pinfunction "1_1") (pintype "passive"))
      (node (ref "R31") (pin "1") (pinfunction "1_1") (pintype "passive"))
      (node (ref "R34") (pin "2") (pinfunction "2_2") (pintype "passive"))
      (node (ref "U2") (pin "1") (pinfunction "VBAT_1") (pintype "passive"))
      (node (ref "U2") (pin "24") (pinfunction "VDD_1_24") (pintype "passive"))
      (node (ref "U2") (pin "36") (pinfunction "VDD_2_36") (pintype "passive"))
      (node (ref "U2") (pin "48") (pinfunction "VDD_3_48") (pintype "passive"))
      (node (ref "U2") (pin "9") (pinfunction "VDDA_9") (pintype "passive"))
      (node (ref "U3") (pin "2") (pinfunction "VCC_2") (pintype "passive"))
    )
    (net (code "22") (name "GND") (class "Default")
      (node (ref "C1") (pin "2") (pinfunction "2_2") (pintype "passive"))
      (node (ref "C10") (pin "1") (pinfunction "1_1") (pintype "passive"))
      (node (ref "C11") (pin "1") (pinfunction "1_1") (pintype "passive"))
      (node (ref "C12") (pin "1") (pinfunction "1_1") (pintype "passive"))
      (node (ref "C13") (pin "1") (pinfunction "1_1") (pintype "passive"))
      (node (ref "C14") (pin "1") (pinfunction "1_1") (pintype "passive"))
      (node (ref "C15") (pin "1") (pinfunction "1_1") (pintype "passive"))
      (node (ref "C16") (pin "1") (pinfunction "1_1") (pintype "passive"))
      (node (ref "C17") (pin "2") (pinfunction "2_2") (pintype "passive"))
      (node (ref "C18") (pin "2") (pinfunction "2_2") (pintype "passive"))
      (node (ref "C19") (pin "2") (pinfunction "2_2") (pintype "passive"))
      (node (ref "C2") (pin "2") (pinfunction "2_2") (pintype "passive"))
      (node (ref "C20") (pin "2") (pinfunction "2_2") (pintype "passive"))
      (node (ref "C21") (pin "2") (pinfunction "2_2") (pintype "passive"))
      (node (ref "C24") (pin "1") (pinfunction "1_1") (pintype "passive"))
      (node (ref "C25") (pin "1") (pinfunction "1_1") (pintype "passive"))
      (node (ref "C26") (pin "1") (pinfunction "1_1") (pintype "passive"))
      (node (ref "C27") (pin "1") (pinfunction "1_1") (pintype "passive"))
      (node (ref "C28") (pin "1") (pinfunction "1_1") (pintype "passive"))
      (node (ref "C29") (pin "1") (pinfunction "1_1") (pintype "passive"))
      (node (ref "C3") (pin "2") (pinfunction "2_2") (pintype "passive"))
      (node (ref "C30") (pin "1") (pinfunction "1_1") (pintype "passive"))
      (node (ref "C31") (pin "1") (pinfunction "1_1") (pintype "passive"))
      (node (ref "C32") (pin "1") (pinfunction "1_1") (pintype "passive"))
      (node (ref "C33") (pin "1") (pinfunction "1_1") (pintype "passive"))
      (node (ref "C34") (pin "1") (pinfunction "1_1") (pintype "passive"))
      (node (ref "C35") (pin "1") (pinfunction "1_1") (pintype "passive"))
      (node (ref "C36") (pin "1") (pinfunction "1_1") (pintype "passive"))
      (node (ref "C38") (pin "1") (pinfunction "1_1") (pintype "passive"))
      (node (ref "C39") (pin "1") (pinfunction "1_1") (pintype "passive"))
      (node (ref "C4") (pin "2") (pinfunction "2_2") (pintype "passive"))
      (node (ref "C40") (pin "1") (pinfunction "1_1") (pintype "passive"))
      (node (ref "C41") (pin "1") (pinfunction "1_1") (pintype "passive"))
      (node (ref "C42") (pin "1") (pinfunction "1_1") (pintype "passive"))
      (node (ref "C43") (pin "1") (pinfunction "1_1") (pintype "passive"))
      (node (ref "C44") (pin "1") (pinfunction "1_1") (pintype "passive"))
      (node (ref "C45") (pin "1") (pinfunction "1_1") (pintype "passive"))
      (node (ref "C46") (pin "1") (pinfunction "1_1") (pintype "passive"))
      (node (ref "C47") (pin "1") (pinfunction "1_1") (pintype "passive"))
      (node (ref "C48") (pin "1") (pinfunction "1_1") (pintype "passive"))
      (node (ref "C5") (pin "2") (pinfunction "2_2") (pintype "passive"))
      (node (ref "C6") (pin "2") (pinfunction "2_2") (pintype "passive"))
      (node (ref "C9") (pin "1") (pinfunction "1_1") (pintype "passive"))
      (node (ref "E1") (pin "2") (pinfunction "2_2") (pintype "passive"))
      (node (ref "E2") (pin "2") (pinfunction "2_2") (pintype "passive"))
      (node (ref "E3") (pin "2") (pinfunction "2_2") (pintype "passive"))
      (node (ref "E4") (pin "2") (pinfunction "2_2") (pintype "passive"))
      (node (ref "IC1") (pin "11") (pinfunction "GND_11") (pintype "passive"))
      (node (ref "J3") (pin "1") (pinfunction "1_1") (pintype "passive"))
      (node (ref "J4") (pin "1") (pinfunction "1_1") (pintype "passive"))
      (node (ref "J9") (pin "2") (pinfunction "2_2") (pintype "passive"))
      (node (ref "JP1") (pin "2") (pinfunction "2_2") (pintype "passive"))
      (node (ref "JP2") (pin "2") (pinfunction "2_2") (pintype "passive"))
      (node (ref "Q3") (pin "3") (pinfunction "S_3") (pintype "passive"))
      (node (ref "Q4") (pin "3") (pinfunction "S_3") (pintype "passive"))
      (node (ref "R16") (pin "1") (pinfunction "1_1") (pintype "passive"))
      (node (ref "R18") (pin "2") (pinfunction "2_2") (pintype "passive"))
      (node (ref "R19") (pin "1") (pinfunction "1_1") (pintype "passive"))
      (node (ref "R21") (pin "2") (pinfunction "2_2") (pintype "passive"))
      (node (ref "R24") (pin "1") (pinfunction "1_1") (pintype "passive"))
      (node (ref "R29") (pin "1") (pinfunction "1_1") (pintype "passive"))
      (node (ref "R32") (pin "2") (pinfunction "2_2") (pintype "passive"))
      (node (ref "R33") (pin "1") (pinfunction "1_1") (pintype "passive"))
      (node (ref "SW1") (pin "1") (pinfunction "1_1") (pintype "passive"))
      (node (ref "SW1") (pin "4") (pinfunction "4_4") (pintype "passive"))
      (node (ref "SW2") (pin "1") (pinfunction "1_1") (pintype "passive"))
      (node (ref "SW2") (pin "4") (pinfunction "4_4") (pintype "passive"))
      (node (ref "SW3") (pin "1") (pinfunction "1_1") (pintype "passive"))
      (node (ref "SW3") (pin "4") (pinfunction "4_4") (pintype "passive"))
      (node (ref "SW4") (pin "1") (pinfunction "1_1") (pintype "passive"))
      (node (ref "SW4") (pin "4") (pinfunction "4_4") (pintype "passive"))
      (node (ref "U1") (pin "5") (pinfunction "INDTA1_5") (pintype "passive"))
      (node (ref "U1") (pin "7") (pinfunction "INDTA2_7") (pintype "passive"))
      (node (ref "U2") (pin "23") (pinfunction "VSS_1_23") (pintype "passive"))
      (node (ref "U2") (pin "35") (pinfunction "VSS_2_35") (pintype "passive"))
      (node (ref "U2") (pin "47") (pinfunction "VSS_3_47") (pintype "passive"))
      (node (ref "U2") (pin "8") (pinfunction "VSSA_8") (pintype "passive"))
      (node (ref "U3") (pin "1") (pinfunction "GND_1") (pintype "passive"))
      (node (ref "USBC1") (pin "0") (pinfunction "0_0") (pintype "passive"))
      (node (ref "USBC1") (pin "A1") (pinfunction "GND_A1") (pintype "passive"))
      (node (ref "USBC1") (pin "A12") (pinfunction "GND_A12") (pintype "passive"))
      (node (ref "USBC1") (pin "B1") (pinfunction "GND_B1") (pintype "passive"))
      (node (ref "USBC1") (pin "B12") (pinfunction "GND_B12") (pintype "passive"))
    )
    (net (code "23") (name "Net-(C9-Pad2)") (class "Default")
      (node (ref "C9") (pin "2") (pinfunction "2_2") (pintype "passive"))
      (node (ref "R5") (pin "1") (pinfunction "1_1") (pintype "passive"))
    )
    (net (code "24") (name "Net-(C10-Pad2)") (class "Default")
      (node (ref "C10") (pin "2") (pinfunction "2_2") (pintype "passive"))
      (node (ref "R6") (pin "1") (pinfunction "1_1") (pintype "passive"))
    )
    (net (code "25") (name "Net-(C27-Pad2)") (class "Default")
      (node (ref "C27") (pin "2") (pinfunction "2_2") (pintype "passive"))
      (node (ref "R14") (pin "2") (pinfunction "2_2") (pintype "passive"))
    )
    (net (code "26") (name "Net-(D2-A)") (class "Default")
      (node (ref "D2") (pin "1") (pinfunction "A_1") (pintype "passive"))
      (node (ref "V2") (pin "2") (pinfunction "Vout_2") (pintype "passive"))
    )
    (net (code "27") (name "Net-(D3-A)") (class "Default")
      (node (ref "D3") (pin "1") (pinfunction "A_1") (pintype "passive"))
      (node (ref "V1") (pin "2") (pinfunction "Vout_2") (pintype "passive"))
    )
    (net (code "28") (name "Net-(IC1-CFG1)") (class "Default")
      (node (ref "IC1") (pin "9") (pinfunction "CFG1_9") (pintype "passive"))
      (node (ref "R32") (pin "1") (pinfunction "1_1") (pintype "passive"))
    )
    (net (code "29") (name "Net-(LED1-A)") (class "Default")
      (node (ref "LED1") (pin "1") (pinfunction "A_1") (pintype "passive"))
      (node (ref "R22") (pin "2") (pinfunction "2_2") (pintype "passive"))
    )
    (net (code "30") (name "Net-(Q1-D)") (class "Default")
      (node (ref "C7") (pin "1") (pinfunction "1_1") (pintype "passive"))
      (node (ref "Q1") (pin "2") (pinfunction "D_2") (pintype "passive"))
      (node (ref "R1") (pin "1") (pinfunction "1_1") (pintype "passive"))
      (node (ref "R8") (pin "2") (pinfunction "2_2") (pintype "passive"))
    )
    (net (code "31") (name "Net-(Q1-G)") (class "Default")
      (node (ref "Q1") (pin "1") (pinfunction "G_1") (pintype "passive"))
      (node (ref "R3") (pin "1") (pinfunction "1_1") (pintype "passive"))
    )
    (net (code "32") (name "Net-(Q1-S)") (class "Default")
      (node (ref "C22") (pin "1") (pinfunction "1_1") (pintype "passive"))
      (node (ref "L1") (pin "1") (pinfunction "1_1") (pintype "passive"))
      (node (ref "Q1") (pin "3") (pinfunction "S_3") (pintype "passive"))
      (node (ref "Q4") (pin "2") (pinfunction "D_2") (pintype "passive"))
      (node (ref "R5") (pin "2") (pinfunction "2_2") (pintype "passive"))
      (node (ref "U1") (pin "30") (pinfunction "SW1_30") (pintype "passive"))
    )
    (net (code "33") (name "Net-(Q2-D)") (class "Default")
      (node (ref "C8") (pin "2") (pinfunction "2_2") (pintype "passive"))
      (node (ref "Q2") (pin "2") (pinfunction "D_2") (pintype "passive"))
      (node (ref "R2") (pin "2") (pinfunction "2_2") (pintype "passive"))
      (node (ref "R9") (pin "2") (pinfunction "2_2") (pintype "passive"))
    )
    (net (code "34") (name "Net-(Q2-G)") (class "Default")
      (node (ref "Q2") (pin "1") (pinfunction "G_1") (pintype "passive"))
      (node (ref "R4") (pin "2") (pinfunction "2_2") (pintype "passive"))
    )
    (net (code "35") (name "Net-(Q2-S)") (class "Default")
      (node (ref "C23") (pin "2") (pinfunction "2_2") (pintype "passive"))
      (node (ref "L1") (pin "2") (pinfunction "2_2") (pintype "passive"))
      (node (ref "Q2") (pin "3") (pinfunction "S_3") (pintype "passive"))
      (node (ref "Q3") (pin "2") (pinfunction "D_2") (pintype "passive"))
      (node (ref "R6") (pin "2") (pinfunction "2_2") (pintype "passive"))
      (node (ref "U1") (pin "26") (pinfunction "SW2_26") (pintype "passive"))
    )
    (net (code "36") (name "Net-(Q3-G)") (class "Default")
      (node (ref "Q3") (pin "1") (pinfunction "G_1") (pintype "passive"))
      (node (ref "R12") (pin "2") (pinfunction "2_2") (pintype "passive"))
    )
    (net (code "37") (name "Net-(Q4-G)") (class "Default")
      (node (ref "Q4") (pin "1") (pinfunction "G_1") (pintype "passive"))
      (node (ref "R11") (pin "1") (pinfunction "1_1") (pintype "passive"))
    )
    (net (code "38") (name "Net-(R13-Pad2)") (class "Default")
      (node (ref "R13") (pin "2") (pinfunction "2_2") (pintype "passive"))
      (node (ref "RP1") (pin "2") (pinfunction "2_2") (pintype "passive"))
    )
    (net (code "39") (name "Net-(R17-Pad2)") (class "Default")
      (node (ref "R17") (pin "2") (pinfunction "2_2") (pintype "passive"))
      (node (ref "R18") (pin "1") (pinfunction "1_1") (pintype "passive"))
    )
    (net (code "40") (name "Net-(U1-5.5V-VDRV)") (class "Default")
      (node (ref "C21") (pin "1") (pinfunction "1_1") (pintype "passive"))
      (node (ref "U1") (pin "28") (pinfunction "5.5V-VDRV_28") (pintype "passive"))
    )
    (net (code "41") (name "Net-(U1-5V-VCC)") (class "Default")
      (node (ref "C24") (pin "2") (pinfunction "2_2") (pintype "passive"))
      (node (ref "U1") (pin "19") (pinfunction "5V-VCC_19") (pintype "passive"))
    )
    (net (code "42") (name "Net-(U1-BSSET)") (class "Default")
      (node (ref "R29") (pin "2") (pinfunction "2_2") (pintype "passive"))
      (node (ref "U1") (pin "14") (pinfunction "BSSET_14") (pintype "passive"))
    )
    (net (code "43") (name "Net-(U1-BST1)") (class "Default")
      (node (ref "C22") (pin "2") (pinfunction "2_2") (pintype "passive"))
      (node (ref "U1") (pin "31") (pinfunction "BST1_31") (pintype "passive"))
    )
    (net (code "44") (name "Net-(U1-BST2)") (class "Default")
      (node (ref "C23") (pin "1") (pinfunction "1_1") (pintype "passive"))
      (node (ref "U1") (pin "25") (pinfunction "BST2_25") (pintype "passive"))
    )
    (net (code "45") (name "Net-(U1-COMP1)") (class "Default")
      (node (ref "C26") (pin "2") (pinfunction "2_2") (pintype "passive"))
      (node (ref "C28") (pin "2") (pinfunction "2_2") (pintype "passive"))
      (node (ref "R15") (pin "1") (pinfunction "1_1") (pintype "passive"))
      (node (ref "U1") (pin "18") (pinfunction "COMP1_18") (pintype "passive"))
    )
    (net (code "46") (name "Net-(U1-COMP2)") (class "Default")
      (node (ref "C25") (pin "2") (pinfunction "2_2") (pintype "passive"))
      (node (ref "R14") (pin "1") (pinfunction "1_1") (pintype "passive"))
      (node (ref "U1") (pin "17") (pinfunction "COMP2_17") (pintype "passive"))
    )
    (net (code "47") (name "Net-(U1-CSN-_VBAT)") (class "Default")
      (node (ref "C20") (pin "1") (pinfunction "1_1") (pintype "passive"))
      (node (ref "R10") (pin "1") (pinfunction "1_1") (pintype "passive"))
      (node (ref "U1") (pin "20") (pinfunction "CSN-_VBAT_20") (pintype "passive"))
    )
    (net (code "48") (name "Net-(U1-CSN-_VBUS)") (class "Default")
      (node (ref "C18") (pin "1") (pinfunction "1_1") (pintype "passive"))
      (node (ref "R8") (pin "1") (pinfunction "1_1") (pintype "passive"))
      (node (ref "U1") (pin "1") (pinfunction "CSN-_VBUS_1") (pintype "passive"))
    )
    (net (code "49") (name "Net-(U1-CSP+_VBAT)") (class "Default")
      (node (ref "C19") (pin "1") (pinfunction "1_1") (pintype "passive"))
      (node (ref "R9") (pin "1") (pinfunction "1_1") (pintype "passive"))
      (node (ref "U1") (pin "21") (pinfunction "CSP+_VBAT_21") (pintype "passive"))
    )
    (net (code "50") (name "Net-(U1-CSP+_VBUS)") (class "Default")
      (node (ref "C17") (pin "1") (pinfunction "1_1") (pintype "passive"))
      (node (ref "R7") (pin "1") (pinfunction "1_1") (pintype "passive"))
      (node (ref "U1") (pin "2") (pinfunction "CSP+_VBUS_2") (pintype "passive"))
    )
    (net (code "51") (name "Net-(U1-HD1)") (class "Default")
      (node (ref "J5") (pin "1") (pinfunction "1_1") (pintype "passive"))
      (node (ref "R3") (pin "2") (pinfunction "2_2") (pintype "passive"))
      (node (ref "U1") (pin "32") (pinfunction "HD1_32") (pintype "passive"))
    )
    (net (code "52") (name "Net-(U1-HD2)") (class "Default")
      (node (ref "J6") (pin "1") (pinfunction "1_1") (pintype "passive"))
      (node (ref "R4") (pin "1") (pinfunction "1_1") (pintype "passive"))
      (node (ref "U1") (pin "24") (pinfunction "HD2_24") (pintype "passive"))
    )
    (net (code "53") (name "Net-(U1-LD1)") (class "Default")
      (node (ref "J7") (pin "1") (pinfunction "1_1") (pintype "passive"))
      (node (ref "R11") (pin "2") (pinfunction "2_2") (pintype "passive"))
      (node (ref "U1") (pin "29") (pinfunction "LD1_29") (pintype "passive"))
    )
    (net (code "54") (name "Net-(U1-LD2)") (class "Default")
      (node (ref "J8") (pin "1") (pinfunction "1_1") (pintype "passive"))
      (node (ref "R12") (pin "1") (pinfunction "1_1") (pintype "passive"))
      (node (ref "U1") (pin "27") (pinfunction "LD2_27") (pintype "passive"))
    )
    (net (code "55") (name "Net-(U1-LSET)") (class "Default")
      (node (ref "R16") (pin "2") (pinfunction "2_2") (pintype "passive"))
      (node (ref "U1") (pin "15") (pinfunction "LSET_15") (pintype "passive"))
    )
    (net (code "56") (name "Net-(U2-BOOT0)") (class "Default")
      (node (ref "R21") (pin "1") (pinfunction "1_1") (pintype "passive"))
      (node (ref "U2") (pin "44") (pinfunction "BOOT0_44") (pintype "passive"))
    )
    (net (code "57") (name "Net-(V1-ADJ)") (class "Default")
      (node (ref "R19") (pin "2") (pinfunction "2_2") (pintype "passive"))
      (node (ref "R20") (pin "1") (pinfunction "1_1") (pintype "passive"))
      (node (ref "V1") (pin "1") (pinfunction "ADJ_1") (pintype "passive"))
    )
    (net (code "58") (name "Net-(V2-ADJ)") (class "Default")
      (node (ref "R33") (pin "2") (pinfunction "2_2") (pintype "passive"))
      (node (ref "R34") (pin "1") (pinfunction "1_1") (pintype "passive"))
      (node (ref "V2") (pin "1") (pinfunction "ADJ_1") (pintype "passive"))
    )
    (net (code "59") (name "VIN") (class "Default")
      (node (ref "C1") (pin "1") (pinfunction "1_1") (pintype "passive"))
      (node (ref "C11") (pin "2") (pinfunction "2_2") (pintype "passive"))
      (node (ref "C12") (pin "2") (pinfunction "2_2") (pintype "passive"))
      (node (ref "C13") (pin "2") (pinfunction "2_2") (pintype "passive"))
      (node (ref "C2") (pin "1") (pinfunction "1_1") (pintype "passive"))
      (node (ref "C29") (pin "2") (pinfunction "2_2") (pintype "passive"))
      (node (ref "C3") (pin "1") (pinfunction "1_1") (pintype "passive"))
      (node (ref "C30") (pin "2") (pinfunction "2_2") (pintype "passive"))
      (node (ref "C7") (pin "2") (pinfunction "2_2") (pintype "passive"))
      (node (ref "D1") (pin "2") (pinfunction "K_2") (pintype "passive"))
      (node (ref "E1") (pin "1") (pinfunction "1_1") (pintype "passive"))
      (node (ref "E2") (pin "1") (pinfunction "1_1") (pintype "passive"))
      (node (ref "J1") (pin "1") (pinfunction "1_1") (pintype "passive"))
      (node (ref "JP1") (pin "1") (pinfunction "1_1") (pintype "passive"))
      (node (ref "R1") (pin "2") (pinfunction "2_2") (pintype "passive"))
      (node (ref "R13") (pin "1") (pinfunction "1_1") (pintype "passive"))
      (node (ref "R7") (pin "2") (pinfunction "2_2") (pintype "passive"))
      (node (ref "U1") (pin "3") (pinfunction "VBUS_3") (pintype "passive"))
      (node (ref "U1") (pin "9") (pinfunction "INDTA3_9") (pintype "passive"))
      (node (ref "V1") (pin "3") (pinfunction "Vin_3") (pintype "passive"))
    )
    (net (code "60") (name "VOUT") (class "Default")
      (node (ref "C14") (pin "2") (pinfunction "2_2") (pintype "passive"))
      (node (ref "C15") (pin "2") (pinfunction "2_2") (pintype "passive"))
      (node (ref "C16") (pin "2") (pinfunction "2_2") (pintype "passive"))
      (node (ref "C4") (pin "1") (pinfunction "1_1") (pintype "passive"))
      (node (ref "C45") (pin "2") (pinfunction "2_2") (pintype "passive"))
      (node (ref "C46") (pin "2") (pinfunction "2_2") (pintype "passive"))
      (node (ref "C5") (pin "1") (pinfunction "1_1") (pintype "passive"))
      (node (ref "C6") (pin "1") (pinfunction "1_1") (pintype "passive"))
      (node (ref "C8") (pin "1") (pinfunction "1_1") (pintype "passive"))
      (node (ref "E3") (pin "1") (pinfunction "1_1") (pintype "passive"))
      (node (ref "E4") (pin "1") (pinfunction "1_1") (pintype "passive"))
      (node (ref "J2") (pin "1") (pinfunction "1_1") (pintype "passive"))
      (node (ref "JP2") (pin "1") (pinfunction "1_1") (pintype "passive"))
      (node (ref "R10") (pin "2") (pinfunction "2_2") (pintype "passive"))
      (node (ref "R2") (pin "1") (pinfunction "1_1") (pintype "passive"))
      (node (ref "U1") (pin "23") (pinfunction "VBAT_23") (pintype "passive"))
      (node (ref "V2") (pin "3") (pinfunction "Vin_3") (pintype "passive"))
    )
    (net (code "61") (name "unconnected-(IC1-CFG2{slash}SCL-Pad2)") (class "Default")
      (node (ref "IC1") (pin "2") (pinfunction "CFG2/SCL_2") (pintype "passive+no_connect"))
    )
    (net (code "62") (name "unconnected-(IC1-CFG3{slash}SDA-Pad3)") (class "Default")
      (node (ref "IC1") (pin "3") (pinfunction "CFG3/SDA_3") (pintype "passive+no_connect"))
    )
    (net (code "63") (name "unconnected-(IC1-PG-Pad10)") (class "Default")
      (node (ref "IC1") (pin "10") (pinfunction "PG_10") (pintype "passive+no_connect"))
    )
    (net (code "64") (name "unconnected-(R15-Pad2)") (class "Default")
      (node (ref "R15") (pin "2") (pinfunction "2_2") (pintype "passive"))
    )
    (net (code "65") (name "unconnected-(RP1-Pad3)") (class "Default")
      (node (ref "RP1") (pin "3") (pinfunction "3_3") (pintype "passive+no_connect"))
    )
    (net (code "66") (name "unconnected-(U1-GATEA1-Pad4)") (class "Default")
      (node (ref "U1") (pin "4") (pinfunction "GATEA1_4") (pintype "passive+no_connect"))
    )
    (net (code "67") (name "unconnected-(U1-GATEA2-Pad6)") (class "Default")
      (node (ref "U1") (pin "6") (pinfunction "GATEA2_6") (pintype "passive+no_connect"))
    )
    (net (code "68") (name "unconnected-(U1-GATEA3-Pad8)") (class "Default")
      (node (ref "U1") (pin "8") (pinfunction "GATEA3_8") (pintype "passive+no_connect"))
    )
    (net (code "69") (name "unconnected-(U1-NC-Pad22)") (class "Default")
      (node (ref "U1") (pin "22") (pinfunction "NC_22") (pintype "passive+no_connect"))
    )
    (net (code "70") (name "unconnected-(U1-NTC-Pad16)") (class "Default")
      (node (ref "U1") (pin "16") (pinfunction "NTC_16") (pintype "passive+no_connect"))
    )
    (net (code "71") (name "unconnected-(U2-PA0{slash}WKUP{slash}ADC123_IN0{slash}T2C1ETR{slash}T5C1{slash}T8ETR-Pad10)") (class "Default")
      (node (ref "U2") (pin "10") (pinfunction "PA0/WKUP/ADC123_IN0/T2C1ETR/T5C1/T8ETR_10") (pintype "passive"))
    )
    (net (code "72") (name "unconnected-(U2-PA1{slash}ADC123_IN1{slash}T5C2{slash}T2C2-Pad11)") (class "Default")
      (node (ref "U2") (pin "11") (pinfunction "PA1/ADC123_IN1/T5C2/T2C2_11") (pintype "passive"))
    )
    (net (code "73") (name "unconnected-(U2-PA2{slash}ADC123_IN2{slash}USART2_Tx{slash}T5C3{slash}T2C3-Pad12)") (class "Default")
      (node (ref "U2") (pin "12") (pinfunction "PA2/ADC123_IN2/USART2_Tx/T5C3/T2C3_12") (pintype "passive"))
    )
    (net (code "74") (name "unconnected-(U2-PA5{slash}ADC123_IN5{slash}DAC_OUT2{slash}SPI1_SCK-Pad15)") (class "Default")
      (node (ref "U2") (pin "15") (pinfunction "PA5/ADC123_IN5/DAC_OUT2/SPI1_SCK_15") (pintype "passive"))
    )
    (net (code "75") (name "unconnected-(U2-PA6{slash}ADC123_IN6{slash}SPI1_MISO{slash}T8T1BKIN{slash}T3C1-Pad16)") (class "Default")
      (node (ref "U2") (pin "16") (pinfunction "PA6/ADC123_IN6/SPI1_MISO/T8T1BKIN/T3C1_16") (pintype "passive"))
    )
    (net (code "76") (name "unconnected-(U2-PA7{slash}ADC123_IN7{slash}SPI1_MOSI{slash}T8C1N{slash}T3C2{slash}T1C1N-Pad17)") (class "Default")
      (node (ref "U2") (pin "17") (pinfunction "PA7/ADC123_IN7/SPI1_MOSI/T8C1N/T3C2/T1C1N_17") (pintype "passive"))
    )
    (net (code "77") (name "unconnected-(U2-PA8{slash}T1C1{slash}MCO-Pad29)") (class "Default")
      (node (ref "U2") (pin "29") (pinfunction "PA8/T1C1/MCO_29") (pintype "passive"))
    )
    (net (code "78") (name "unconnected-(U2-PA9{slash}T1C2{slash}USART1_Tx-Pad30)") (class "Default")
      (node (ref "U2") (pin "30") (pinfunction "PA9/T1C2/USART1_Tx_30") (pintype "passive"))
    )
    (net (code "79") (name "unconnected-(U2-PA10{slash}T1C3{slash}USART1_Rx-Pad31)") (class "Default")
      (node (ref "U2") (pin "31") (pinfunction "PA10/T1C3/USART1_Rx_31") (pintype "passive"))
    )
    (net (code "80") (name "unconnected-(U2-PA11{slash}CAN_Rx{slash}T1C4{slash}USBDM-Pad32)") (class "Default")
      (node (ref "U2") (pin "32") (pinfunction "PA11/CAN_Rx/T1C4/USBDM_32") (pintype "passive"))
    )
    (net (code "81") (name "unconnected-(U2-PA12{slash}CAN_Tx{slash}T1ETR{slash}USBDP-Pad33)") (class "Default")
      (node (ref "U2") (pin "33") (pinfunction "PA12/CAN_Tx/T1ETR/USBDP_33") (pintype "passive"))
    )
    (net (code "82") (name "unconnected-(U2-PA15{slash}JTDI{slash}I2S3_WS{slash}JTDI{slash}T2C1ETR{slash}SPI3_NSS-Pad38)") (class "Default")
      (node (ref "U2") (pin "38") (pinfunction "PA15/JTDI/I2S3_WS/JTDI/T2C1ETR/SPI3_NSS_38") (pintype "passive"))
    )
    (net (code "83") (name "unconnected-(U2-PB0{slash}ADC123_IN8{slash}T3C3{slash}T8C2N{slash}T1C2N-Pad18)") (class "Default")
      (node (ref "U2") (pin "18") (pinfunction "PB0/ADC123_IN8/T3C3/T8C2N/T1C2N_18") (pintype "passive"))
    )
    (net (code "84") (name "unconnected-(U2-PB1{slash}ADC123_IN9{slash}T3C4{slash}T8C3N{slash}T1C3N-Pad19)") (class "Default")
      (node (ref "U2") (pin "19") (pinfunction "PB1/ADC123_IN9/T3C4/T8C3N/T1C3N_19") (pintype "passive"))
    )
    (net (code "85") (name "unconnected-(U2-PB2{slash}BOOT1-Pad20)") (class "Default")
      (node (ref "U2") (pin "20") (pinfunction "PB2/BOOT1_20") (pintype "passive"))
    )
    (net (code "86") (name "unconnected-(U2-PB4{slash}NJTRST{slash}SPI3_MISO{slash}T3C1{slash}SPI1_MISO-Pad40)") (class "Default")
      (node (ref "U2") (pin "40") (pinfunction "PB4/NJTRST/SPI3_MISO/T3C1/SPI1_MISO_40") (pintype "passive"))
    )
    (net (code "87") (name "unconnected-(U2-PB5{slash}I2C1_SMBA{slash}I2S3_SD{slash}SPI3_MOSI{slash}T3C2{slash}SPI1_MOSI-Pad41)") (class "Default")
      (node (ref "U2") (pin "41") (pinfunction "PB5/I2C1_SMBA/I2S3_SD/SPI3_MOSI/T3C2/SPI1_MOSI_41") (pintype "passive"))
    )
    (net (code "88") (name "unconnected-(U2-PB10{slash}USART3_Tx{slash}I2C2_SCL{slash}T2C3-Pad21)") (class "Default")
      (node (ref "U2") (pin "21") (pinfunction "PB10/USART3_Tx/I2C2_SCL/T2C3_21") (pintype "passive"))
    )
    (net (code "89") (name "unconnected-(U2-PB12{slash}I2S2_WS{slash}T1BKIN{slash}SPI2_NSS{slash}I2C2_SMBA-Pad25)") (class "Default")
      (node (ref "U2") (pin "25") (pinfunction "PB12/I2S2_WS/T1BKIN/SPI2_NSS/I2C2_SMBA_25") (pintype "passive"))
    )
    (net (code "90") (name "unconnected-(U2-PB13{slash}I2S2_CK{slash}T1CH1N{slash}SPI2_SCK-Pad26)") (class "Default")
      (node (ref "U2") (pin "26") (pinfunction "PB13/I2S2_CK/T1CH1N/SPI2_SCK_26") (pintype "passive"))
    )
    (net (code "91") (name "unconnected-(U2-PB14{slash}T1CH2N{slash}SPI2_MISO-Pad27)") (class "Default")
      (node (ref "U2") (pin "27") (pinfunction "PB14/T1CH2N/SPI2_MISO_27") (pintype "passive"))
    )
    (net (code "92") (name "unconnected-(U2-PB15{slash}I2S2_SD{slash}T1CH3N{slash}SPI2_MOSI-Pad28)") (class "Default")
      (node (ref "U2") (pin "28") (pinfunction "PB15/I2S2_SD/T1CH3N/SPI2_MOSI_28") (pintype "passive"))
    )
    (net (code "93") (name "unconnected-(U2-PC14-OSC32_IN-Pad3)") (class "Default")
      (node (ref "U2") (pin "3") (pinfunction "PC14-OSC32_IN_3") (pintype "passive"))
    )
    (net (code "94") (name "unconnected-(U2-PC15-OSC32_OUT-Pad4)") (class "Default")
      (node (ref "U2") (pin "4") (pinfunction "PC15-OSC32_OUT_4") (pintype "passive"))
    )
    (net (code "95") (name "unconnected-(USBC1-SBU1-PadA8)") (class "Default")
      (node (ref "USBC1") (pin "A8") (pinfunction "SBU1_A8") (pintype "passive+no_connect"))
    )
    (net (code "96") (name "unconnected-(USBC1-SBU2-PadB8)") (class "Default")
      (node (ref "USBC1") (pin "B8") (pinfunction "SBU2_B8") (pintype "passive+no_connect"))
    )
  )
)
